# DS18B20.net
KiCad netlist of a schematic drawn in Altium Designer
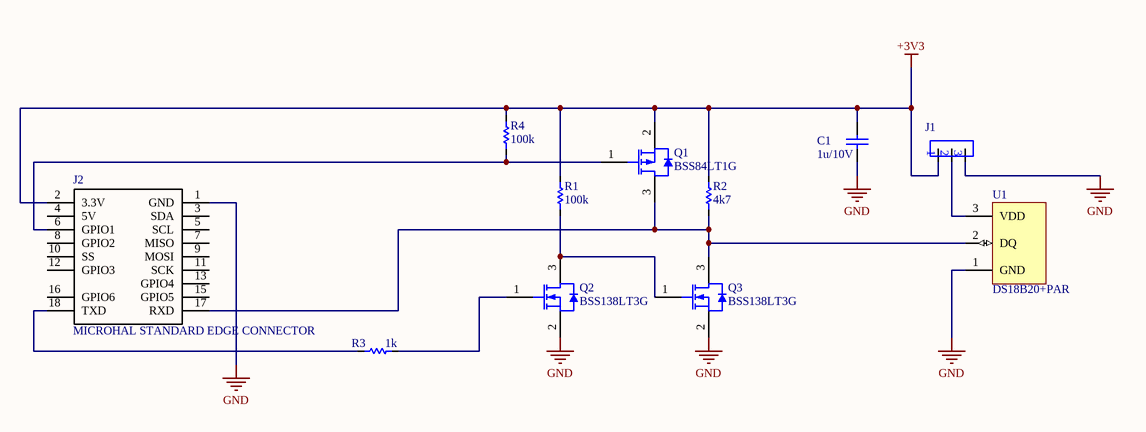
[diagram p0: DS18B20.SchDoc]

(export (version "E")
  (design (tool "Eeschema 10.0.6"))
  (components
    (comp (ref "C1")
      (value "1u/10V")
      (footprint "CAPC2013X140X50ML20T25")
      (description "CAP CER 1UF 10V 10% X7R 0805")
      (libsource (lib "CommunityVault") (part "CMP-126530-2"))
    )
    (comp (ref "J1")
      (value "SYM-52d299a8d8748d15-1")
      (footprint "PCB-vkgeqjtjqx6hhmcxuagx-1")
      (description "AMPMODU 3 Position 2.54 mm Single Row Through-Hole Straight Breakaway Header")
      (libsource (lib "CommunityVault") (part "CMP-740dbf71fd8babca-12"))
    )
    (comp (ref "J2")
      (value "MICROHAL STANDARD EDGE CONNECTOR")
      (footprint "PCB-n61ghpg3sznbl2uw6fwj-1")
      (description "microhal standard edge connector with 17 pins")
      (libsource (lib "CommunityVault") (part "CMP-6a3uyflm72uf0am1b36s-2"))
    )
    (comp (ref "Q1")
      (value "BSS84LT1G")
      (footprint "ONSC-SOT-23-3-318-08")
      (description "MOSFET")
      (libsource (lib "CommunityVault") (part "CMP-10937362-2"))
    )
    (comp (ref "Q2")
      (value "BSS138LT3G")
      (footprint "ONSC-SOT-23-3-318-08_V")
      (description "Power MOSFET, 200 mA, 50 V, N-Channel, 3-Pin SOT-23, Pb-Free, Tape and Reel")
      (libsource (lib "CommunityVault") (part "ONSC-NMOS-G1S2D3-3"))
    )
    (comp (ref "Q3")
      (value "BSS138LT3G")
      (footprint "ONSC-SOT-23-3-318-08_V")
      (description "Power MOSFET, 200 mA, 50 V, N-Channel, 3-Pin SOT-23, Pb-Free, Tape and Reel")
      (libsource (lib "CommunityVault") (part "ONSC-NMOS-G1S2D3-3"))
    )
    (comp (ref "R1")
      (value "100k")
      (footprint "PCB-cmzy4aezi5zhn2bew7lt-1")
      (description "Surface Mount Chip Resistor, Thick Film, AEC-Q200 CRCW Series, 4.7 kohm, 250 mW, 1%, 75 V")
      (fields (field (name "MANUFACTURER PART NUMBER") "CRCW06034K70FKEAHP"))
      (libsource (lib "CommunityVault") (part "CMP-40e08b60e91c9f27-1"))
    )
    (comp (ref "R2")
      (value "4k7")
      (footprint "PCB-cmzy4aezi5zhn2bew7lt-1")
      (description "Surface Mount Chip Resistor, Thick Film, AEC-Q200 CRCW Series, 4.7 kohm, 250 mW, 1%, 75 V")
      (fields (field (name "MANUFACTURER PART NUMBER") "CRCW06034K70FKEAHP"))
      (libsource (lib "CommunityVault") (part "CMP-40e08b60e91c9f27-1"))
    )
    (comp (ref "R3")
      (value "1k")
      (footprint "PCB-cmzy4aezi5zhn2bew7lt-1")
      (description "Surface Mount Chip Resistor, Thick Film, AEC-Q200 CRCW Series, 4.7 kohm, 250 mW, 1%, 75 V")
      (fields (field (name "MANUFACTURER PART NUMBER") "CRCW06034K70FKEAHP"))
      (libsource (lib "CommunityVault") (part "CMP-40e08b60e91c9f27-1"))
    )
    (comp (ref "R4")
      (value "100k")
      (footprint "PCB-cmzy4aezi5zhn2bew7lt-1")
      (description "Surface Mount Chip Resistor, Thick Film, AEC-Q200 CRCW Series, 4.7 kohm, 250 mW, 1%, 75 V")
      (fields (field (name "MANUFACTURER PART NUMBER") "CRCW06034K70FKEAHP"))
      (libsource (lib "CommunityVault") (part "CMP-40e08b60e91c9f27-1"))
    )
    (comp (ref "U1")
      (value "DS18B20+PAR")
      (footprint "Q3+1")
      (libsource (lib "CommunityVault") (part "CMP-978384-4"))
    )
  )
  (nets
    (net (code "1") (name "+3V3") (class "Default")
      (node (ref "C1") (pin "2") (pinfunction "2_2") (pintype "passive"))
      (node (ref "J1") (pin "1") (pinfunction "1_1") (pintype "passive"))
      (node (ref "J2") (pin "2") (pinfunction "3.3V_2") (pintype "passive"))
      (node (ref "Q1") (pin "2") (pinfunction "S_2") (pintype "passive"))
      (node (ref "R1") (pin "2") (pinfunction "2_2") (pintype "passive"))
      (node (ref "R2") (pin "2") (pinfunction "2_2") (pintype "passive"))
      (node (ref "R4") (pin "2") (pinfunction "2_2") (pintype "passive"))
    )
    (net (code "2") (name "GND") (class "Default")
      (node (ref "C1") (pin "1") (pinfunction "1_1") (pintype "passive"))
      (node (ref "J1") (pin "3") (pinfunction "3_3") (pintype "passive"))
      (node (ref "J2") (pin "1") (pinfunction "GND_1") (pintype "passive"))
      (node (ref "Q2") (pin "2") (pinfunction "S_2") (pintype "passive"))
      (node (ref "Q3") (pin "2") (pinfunction "S_2") (pintype "passive"))
      (node (ref "U1") (pin "1") (pinfunction "GND_1") (pintype "power_in"))
    )
    (net (code "3") (name "Net-(J2-GPIO1)") (class "Default")
      (node (ref "J2") (pin "6") (pinfunction "GPIO1_6") (pintype "passive"))
      (node (ref "Q1") (pin "1") (pinfunction "G_1") (pintype "passive"))
      (node (ref "R4") (pin "1") (pinfunction "1_1") (pintype "passive"))
    )
    (net (code "4") (name "Net-(J2-RXD)") (class "Default")
      (node (ref "J2") (pin "17") (pinfunction "RXD_17") (pintype "passive"))
      (node (ref "Q1") (pin "3") (pinfunction "D_3") (pintype "passive"))
      (node (ref "Q3") (pin "3") (pinfunction "D_3") (pintype "passive"))
      (node (ref "R2") (pin "1") (pinfunction "1_1") (pintype "passive"))
      (node (ref "U1") (pin "2") (pinfunction "DQ_2") (pintype "bidirectional"))
    )
    (net (code "5") (name "Net-(J2-TXD)") (class "Default")
      (node (ref "J2") (pin "18") (pinfunction "TXD_18") (pintype "passive"))
      (node (ref "R3") (pin "2") (pinfunction "2_2") (pintype "passive"))
    )
    (net (code "6") (name "Net-(Q2-D)") (class "Default")
      (node (ref "Q2") (pin "3") (pinfunction "D_3") (pintype "passive"))
      (node (ref "Q3") (pin "1") (pinfunction "G_1") (pintype "passive"))
      (node (ref "R1") (pin "1") (pinfunction "1_1") (pintype "passive"))
    )
    (net (code "7") (name "Net-(Q2-G)") (class "Default")
      (node (ref "Q2") (pin "1") (pinfunction "G_1") (pintype "passive"))
      (node (ref "R3") (pin "1") (pinfunction "1_1") (pintype "passive"))
    )
    (net (code "8") (name "Net-(U1-VDD)") (class "Default")
      (node (ref "J1") (pin "2") (pinfunction "2_2") (pintype "passive"))
      (node (ref "U1") (pin "3") (pinfunction "VDD_3") (pintype "power_in"))
    )
    (net (code "9") (name "unconnected-(J2-5V-Pad4)") (class "Default")
      (node (ref "J2") (pin "4") (pinfunction "5V_4") (pintype "passive"))
    )
    (net (code "10") (name "unconnected-(J2-GPIO2-Pad8)") (class "Default")
      (node (ref "J2") (pin "8") (pinfunction "GPIO2_8") (pintype "passive"))
    )
    (net (code "11") (name "unconnected-(J2-GPIO3-Pad12)") (class "Default")
      (node (ref "J2") (pin "12") (pinfunction "GPIO3_12") (pintype "passive"))
    )
    (net (code "12") (name "unconnected-(J2-GPIO4-Pad13)") (class "Default")
      (node (ref "J2") (pin "13") (pinfunction "GPIO4_13") (pintype "passive"))
    )
    (net (code "13") (name "unconnected-(J2-GPIO5-Pad15)") (class "Default")
      (node (ref "J2") (pin "15") (pinfunction "GPIO5_15") (pintype "passive"))
    )
    (net (code "14") (name "unconnected-(J2-GPIO6-Pad16)") (class "Default")
      (node (ref "J2") (pin "16") (pinfunction "GPIO6_16") (pintype "passive"))
    )
    (net (code "15") (name "unconnected-(J2-MISO-Pad7)") (class "Default")
      (node (ref "J2") (pin "7") (pinfunction "MISO_7") (pintype "passive"))
    )
    (net (code "16") (name "unconnected-(J2-MOSI-Pad9)") (class "Default")
      (node (ref "J2") (pin "9") (pinfunction "MOSI_9") (pintype "passive"))
    )
    (net (code "17") (name "unconnected-(J2-SCK-Pad11)") (class "Default")
      (node (ref "J2") (pin "11") (pinfunction "SCK_11") (pintype "passive"))
    )
    (net (code "18") (name "unconnected-(J2-SCL-Pad5)") (class "Default")
      (node (ref "J2") (pin "5") (pinfunction "SCL_5") (pintype "passive"))
    )
    (net (code "19") (name "unconnected-(J2-SDA-Pad3)") (class "Default")
      (node (ref "J2") (pin "3") (pinfunction "SDA_3") (pintype "passive"))
    )
    (net (code "20") (name "unconnected-(J2-SS-Pad10)") (class "Default")
      (node (ref "J2") (pin "10") (pinfunction "SS_10") (pintype "passive"))
    )
  )
)
